# 03_DAC.net
KiCad netlist of a schematic drawn in Altium Designer
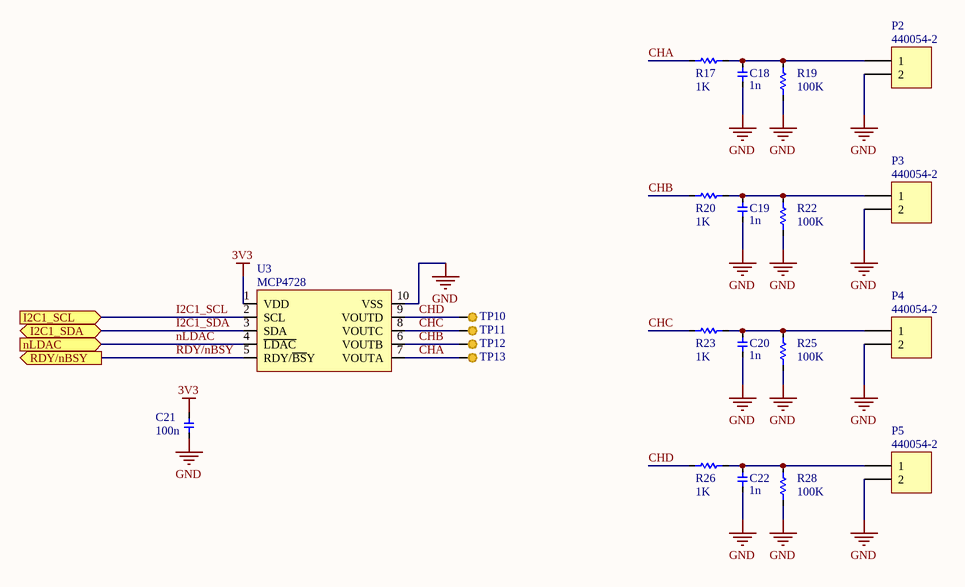
[diagram p0: 03_DAC.SchDoc]

(export (version "E")
  (design (tool "Eeschema 10.0.6"))
  (components
    (comp (ref "C18")
      (value "1n")
      (footprint "Moji Footprintovi:0603 - CAP")
      (description "Capacitor")
      (fields (field (name "Comment") "Cap"))
      (libsource (lib "Moji Schematici") (part "Cap"))
    )
    (comp (ref "C19")
      (value "1n")
      (footprint "Moji Footprintovi:0603 - CAP")
      (description "Capacitor")
      (fields (field (name "Comment") "Cap"))
      (libsource (lib "Moji Schematici") (part "Cap"))
    )
    (comp (ref "C20")
      (value "1n")
      (footprint "Moji Footprintovi:0603 - CAP")
      (description "Capacitor")
      (fields (field (name "Comment") "Cap"))
      (libsource (lib "Moji Schematici") (part "Cap"))
    )
    (comp (ref "C21")
      (value "100n")
      (footprint "Moji Footprintovi:0603 - CAP")
      (description "Capacitor")
      (fields
        (field (name "MANUFACTURER") "AVX Corporation")
        (field (name "MANUFACTURER PART NUMBER") "06035C104KAT2A")
      )
      (libsource (lib "Moji Schematici") (part "Cap"))
    )
    (comp (ref "C22")
      (value "1n")
      (footprint "Moji Footprintovi:0603 - CAP")
      (description "Capacitor")
      (fields (field (name "Comment") "Cap"))
      (libsource (lib "Moji Schematici") (part "Cap"))
    )
    (comp (ref "P2")
      (value "440054-2")
      (footprint "Moji Footprintovi:HEADER-2mm-2Pos")
      (description "CONN HEADER VERT 2POS 2MM")
      (fields (field (name "MANUFACTURER") "TE Connectivity AMP Connectors"))
      (libsource (lib "Moji Schematici") (part "440054-2"))
    )
    (comp (ref "P3")
      (value "440054-2")
      (footprint "Moji Footprintovi:HEADER-2mm-2Pos")
      (description "CONN HEADER VERT 2POS 2MM")
      (fields (field (name "MANUFACTURER") "TE Connectivity AMP Connectors"))
      (libsource (lib "Moji Schematici") (part "440054-2"))
    )
    (comp (ref "P4")
      (value "440054-2")
      (footprint "Moji Footprintovi:HEADER-2mm-2Pos")
      (description "CONN HEADER VERT 2POS 2MM")
      (fields (field (name "MANUFACTURER") "TE Connectivity AMP Connectors"))
      (libsource (lib "Moji Schematici") (part "440054-2"))
    )
    (comp (ref "P5")
      (value "440054-2")
      (footprint "Moji Footprintovi:HEADER-2mm-2Pos")
      (description "CONN HEADER VERT 2POS 2MM")
      (fields (field (name "MANUFACTURER") "TE Connectivity AMP Connectors"))
      (libsource (lib "Moji Schematici") (part "440054-2"))
    )
    (comp (ref "R17")
      (value "1K")
      (footprint "Moji Footprintovi:0603")
      (description "Resistor")
      (fields (field (name "Comment") "Res"))
      (libsource (lib "Moji Schematici") (part "Res"))
    )
    (comp (ref "R19")
      (value "100K")
      (footprint "Moji Footprintovi:0603")
      (description "Resistor")
      (fields
        (field (name "DISTRIBUTOR PART NUMBER") "311-100KHRCT-ND")
        (field (name "MANUFACTURER") "Yageo")
      )
      (libsource (lib "Moji Schematici") (part "Res"))
    )
    (comp (ref "R20")
      (value "1K")
      (footprint "Moji Footprintovi:0603")
      (description "Resistor")
      (fields (field (name "Comment") "Res"))
      (libsource (lib "Moji Schematici") (part "Res"))
    )
    (comp (ref "R22")
      (value "100K")
      (footprint "Moji Footprintovi:0603")
      (description "Resistor")
      (fields
        (field (name "DISTRIBUTOR PART NUMBER") "311-100KHRCT-ND")
        (field (name "MANUFACTURER") "Yageo")
      )
      (libsource (lib "Moji Schematici") (part "Res"))
    )
    (comp (ref "R23")
      (value "1K")
      (footprint "Moji Footprintovi:0603")
      (description "Resistor")
      (fields (field (name "Comment") "Res"))
      (libsource (lib "Moji Schematici") (part "Res"))
    )
    (comp (ref "R25")
      (value "100K")
      (footprint "Moji Footprintovi:0603")
      (description "Resistor")
      (fields
        (field (name "DISTRIBUTOR PART NUMBER") "311-100KHRCT-ND")
        (field (name "MANUFACTURER") "Yageo")
      )
      (libsource (lib "Moji Schematici") (part "Res"))
    )
    (comp (ref "R26")
      (value "1K")
      (footprint "Moji Footprintovi:0603")
      (description "Resistor")
      (fields (field (name "Comment") "Res"))
      (libsource (lib "Moji Schematici") (part "Res"))
    )
    (comp (ref "R28")
      (value "100K")
      (footprint "Moji Footprintovi:0603")
      (description "Resistor")
      (fields
        (field (name "DISTRIBUTOR PART NUMBER") "311-100KHRCT-ND")
        (field (name "MANUFACTURER") "Yageo")
      )
      (libsource (lib "Moji Schematici") (part "Res"))
    )
    (comp (ref "TP10")
      (value "Test Point 0.6mm")
      (footprint "Moji Footprintovi:TP_SMD_1mm")
      (libsource (lib "Moji Schematici") (part "TP"))
    )
    (comp (ref "TP11")
      (value "Test Point 0.6mm")
      (footprint "Moji Footprintovi:TP_SMD_1mm")
      (libsource (lib "Moji Schematici") (part "TP"))
    )
    (comp (ref "TP12")
      (value "Test Point 0.6mm")
      (footprint "Moji Footprintovi:TP_SMD_1mm")
      (libsource (lib "Moji Schematici") (part "TP"))
    )
    (comp (ref "TP13")
      (value "Test Point 0.6mm")
      (footprint "Moji Footprintovi:TP_SMD_1mm")
      (libsource (lib "Moji Schematici") (part "TP"))
    )
    (comp (ref "U3")
      (value "MCP4728")
      (footprint "Moji Footprintovi:TSSOP50P490X110-10N")
      (description "IC DAC 12BIT W/I2C 10-MSOP")
      (fields
        (field (name "MANUFACTURER") "Microchip Technology")
        (field (name "MANUFACTURER PART NUMBER") "MCP4728T-E/UN")
      )
      (libsource (lib "Moji Schematici") (part "MCP4728"))
    )
  )
  (nets
    (net (code "1") (name "/CHA") (class "Default")
      (node (ref "R17") (pin "1") (pinfunction "1_1") (pintype "passive"))
      (node (ref "TP13") (pin "1") (pinfunction "1_1") (pintype "passive"))
      (node (ref "U3") (pin "7") (pinfunction "VOUTA_7") (pintype "passive"))
    )
    (net (code "2") (name "/CHB") (class "Default")
      (node (ref "R20") (pin "1") (pinfunction "1_1") (pintype "passive"))
      (node (ref "TP12") (pin "1") (pinfunction "1_1") (pintype "passive"))
      (node (ref "U3") (pin "6") (pinfunction "VOUTB_6") (pintype "passive"))
    )
    (net (code "3") (name "/CHC") (class "Default")
      (node (ref "R23") (pin "1") (pinfunction "1_1") (pintype "passive"))
      (node (ref "TP11") (pin "1") (pinfunction "1_1") (pintype "passive"))
      (node (ref "U3") (pin "8") (pinfunction "VOUTC_8") (pintype "passive"))
    )
    (net (code "4") (name "/CHD") (class "Default")
      (node (ref "R26") (pin "1") (pinfunction "1_1") (pintype "passive"))
      (node (ref "TP10") (pin "1") (pinfunction "1_1") (pintype "passive"))
      (node (ref "U3") (pin "9") (pinfunction "VOUTD_9") (pintype "passive"))
    )
    (net (code "5") (name "/I2C1_SCL") (class "Default")
      (node (ref "U3") (pin "2") (pinfunction "SCL_2") (pintype "passive"))
    )
    (net (code "6") (name "/I2C1_SDA") (class "Default")
      (node (ref "U3") (pin "3") (pinfunction "SDA_3") (pintype "passive"))
    )
    (net (code "7") (name "/RDY{slash}nBSY") (class "Default")
      (node (ref "U3") (pin "5") (pinfunction "RDY/~{BS}Y_5") (pintype "passive"))
    )
    (net (code "8") (name "/nLDAC") (class "Default")
      (node (ref "U3") (pin "4") (pinfunction "~{LDAC}_4") (pintype "passive"))
    )
    (net (code "9") (name "3V3") (class "Default")
      (node (ref "C21") (pin "2") (pinfunction "2_2") (pintype "passive"))
      (node (ref "U3") (pin "1") (pinfunction "VDD_1") (pintype "passive"))
    )
    (net (code "10") (name "GND") (class "Default")
      (node (ref "C18") (pin "1") (pinfunction "1_1") (pintype "passive"))
      (node (ref "C19") (pin "1") (pinfunction "1_1") (pintype "passive"))
      (node (ref "C20") (pin "1") (pinfunction "1_1") (pintype "passive"))
      (node (ref "C21") (pin "1") (pinfunction "1_1") (pintype "passive"))
      (node (ref "C22") (pin "1") (pinfunction "1_1") (pintype "passive"))
      (node (ref "P2") (pin "2") (pinfunction "2_2") (pintype "passive"))
      (node (ref "P3") (pin "2") (pinfunction "2_2") (pintype "passive"))
      (node (ref "P4") (pin "2") (pinfunction "2_2") (pintype "passive"))
      (node (ref "P5") (pin "2") (pinfunction "2_2") (pintype "passive"))
      (node (ref "R19") (pin "1") (pinfunction "1_1") (pintype "passive"))
      (node (ref "R22") (pin "1") (pinfunction "1_1") (pintype "passive"))
      (node (ref "R25") (pin "1") (pinfunction "1_1") (pintype "passive"))
      (node (ref "R28") (pin "1") (pinfunction "1_1") (pintype "passive"))
      (node (ref "U3") (pin "10") (pinfunction "VSS_10") (pintype "passive"))
    )
    (net (code "11") (name "Net-(C18-Pad2)") (class "Default")
      (node (ref "C18") (pin "2") (pinfunction "2_2") (pintype "passive"))
      (node (ref "P2") (pin "1") (pinfunction "1_1") (pintype "passive"))
      (node (ref "R17") (pin "2") (pinfunction "2_2") (pintype "passive"))
      (node (ref "R19") (pin "2") (pinfunction "2_2") (pintype "passive"))
    )
    (net (code "12") (name "Net-(C19-Pad2)") (class "Default")
      (node (ref "C19") (pin "2") (pinfunction "2_2") (pintype "passive"))
      (node (ref "P3") (pin "1") (pinfunction "1_1") (pintype "passive"))
      (node (ref "R20") (pin "2") (pinfunction "2_2") (pintype "passive"))
      (node (ref "R22") (pin "2") (pinfunction "2_2") (pintype "passive"))
    )
    (net (code "13") (name "Net-(C20-Pad2)") (class "Default")
      (node (ref "C20") (pin "2") (pinfunction "2_2") (pintype "passive"))
      (node (ref "P4") (pin "1") (pinfunction "1_1") (pintype "passive"))
      (node (ref "R23") (pin "2") (pinfunction "2_2") (pintype "passive"))
      (node (ref "R25") (pin "2") (pinfunction "2_2") (pintype "passive"))
    )
    (net (code "14") (name "Net-(C22-Pad2)") (class "Default")
      (node (ref "C22") (pin "2") (pinfunction "2_2") (pintype "passive"))
      (node (ref "P5") (pin "1") (pinfunction "1_1") (pintype "passive"))
      (node (ref "R26") (pin "2") (pinfunction "2_2") (pintype "passive"))
      (node (ref "R28") (pin "2") (pinfunction "2_2") (pintype "passive"))
    )
  )
)
